# uicc.net
KiCad netlist of a schematic drawn in Altium Designer
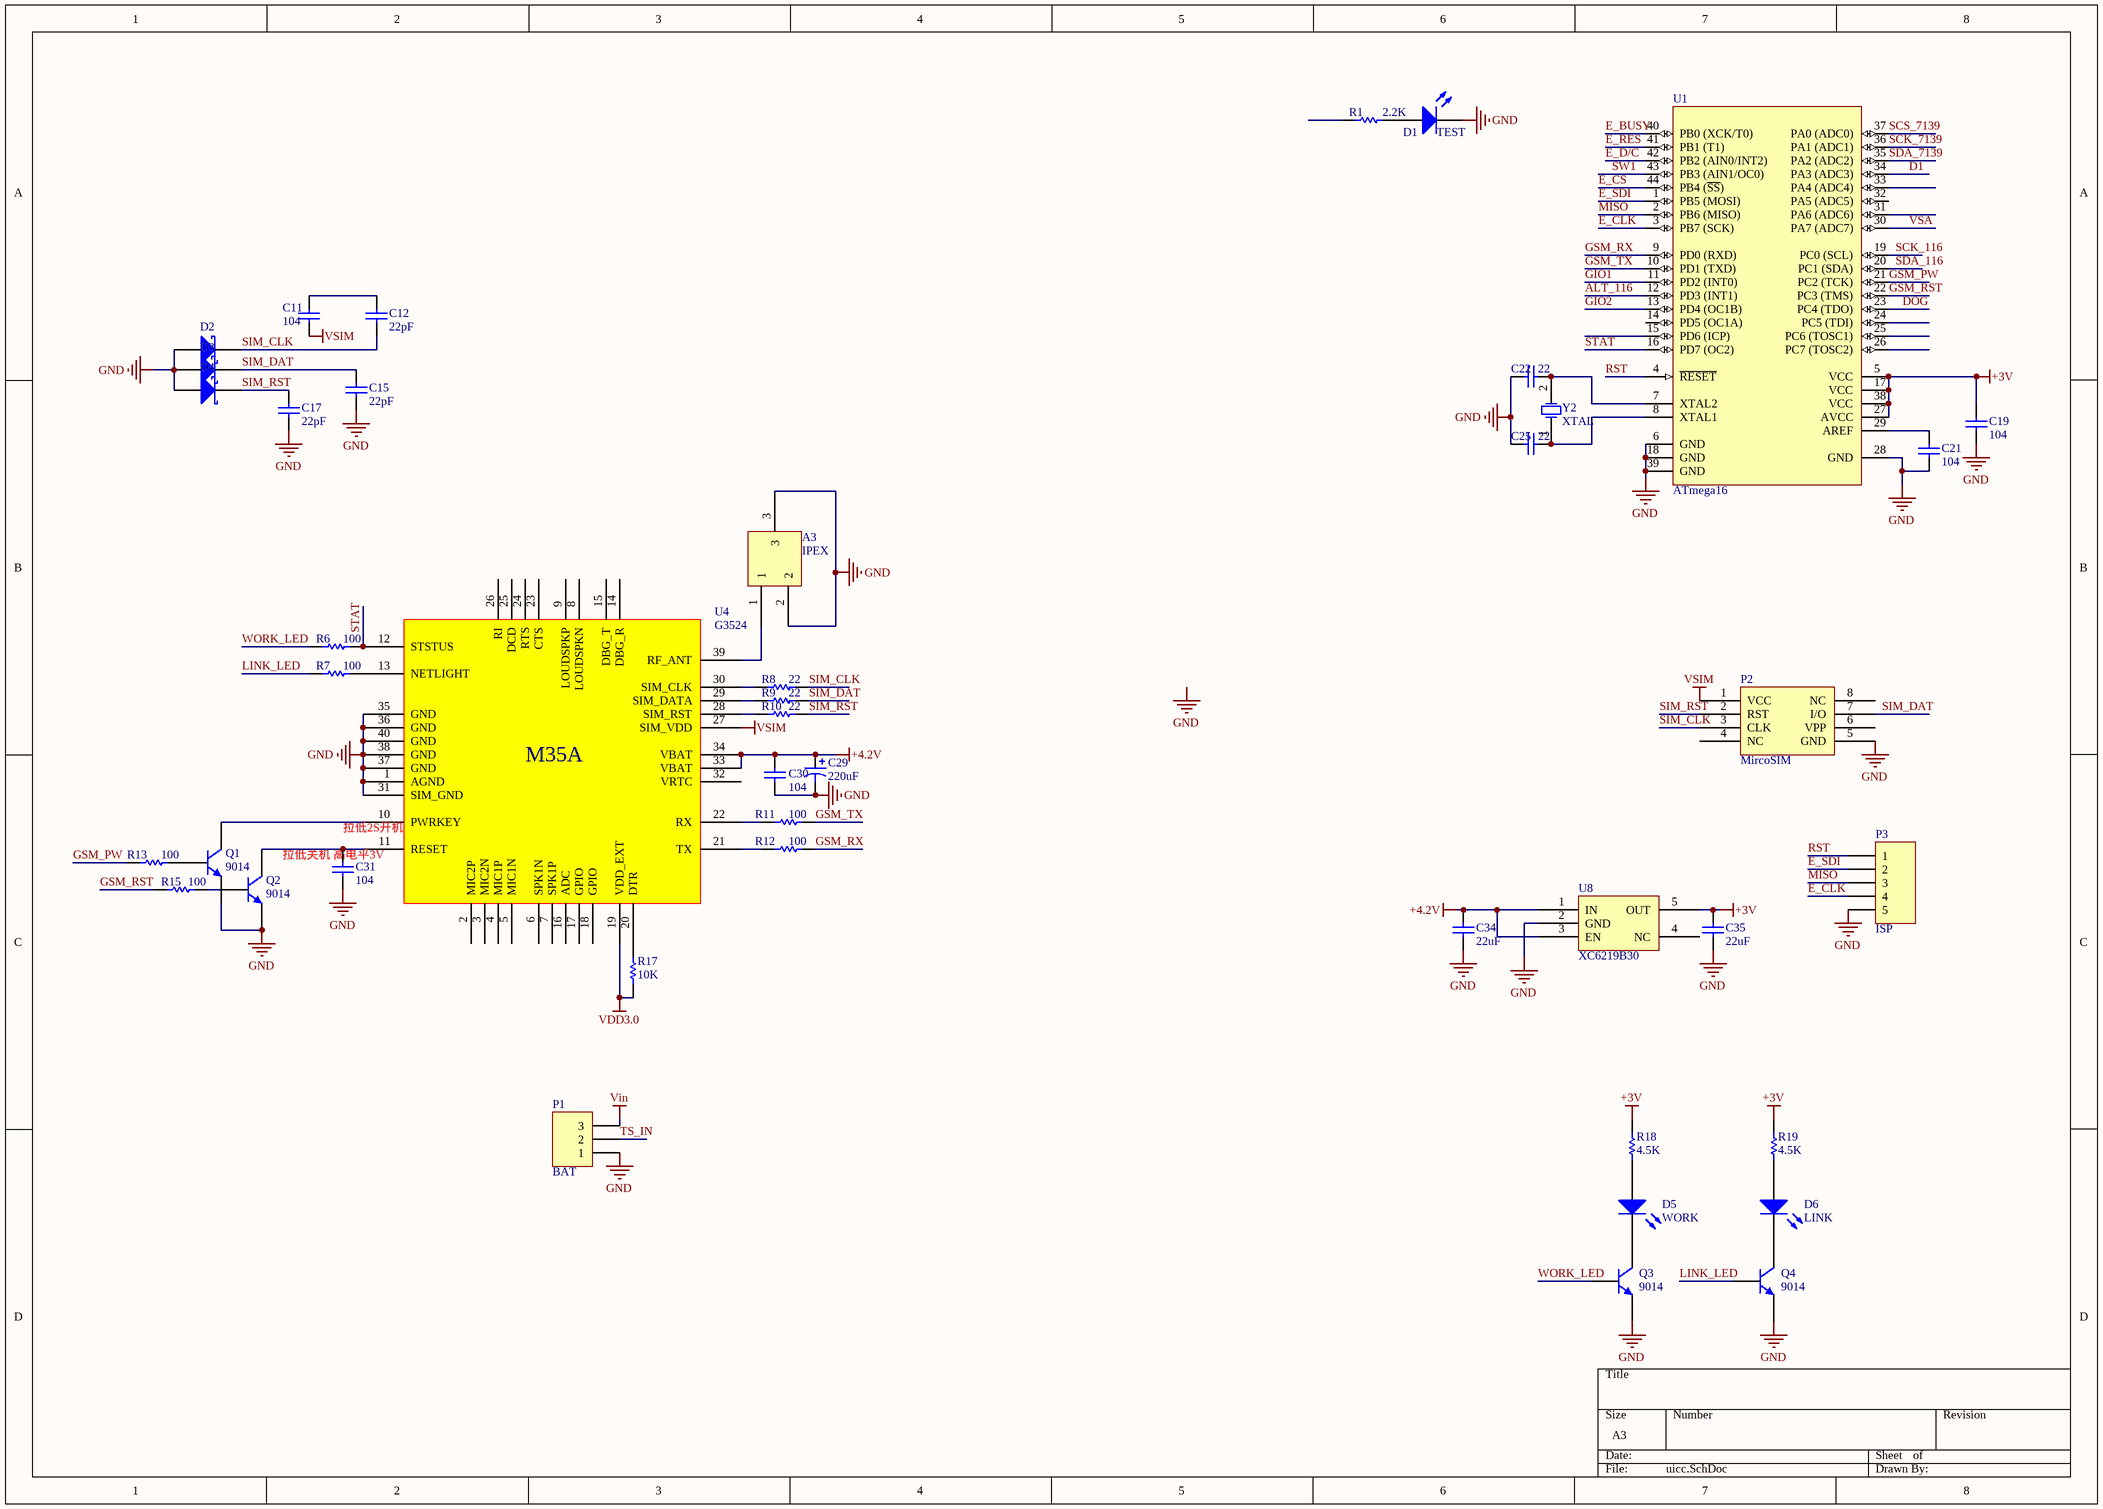
[diagram p0: uicc.SchDoc]

(export (version "E")
  (design (tool "Eeschema 10.0.6"))
  (components
    (comp (ref "A3") (value "IPEX") (footprint "IPEX") (libsource (lib "TANK") (part "IPEX")))
    (comp (ref "C11")
      (value "104")
      (footprint "0603")
      (description "Capacitor")
      (fields (field (name "Comment") "Cap") (field (name "PUBLISHER") "Altium Limited"))
      (libsource (lib "Miscellaneous Devices") (part "Cap"))
    )
    (comp (ref "C12")
      (value "22pF")
      (footprint "0603")
      (description "Capacitor")
      (fields (field (name "Comment") "Cap") (field (name "PUBLISHER") "Altium Limited"))
      (libsource (lib "Miscellaneous Devices") (part "Cap"))
    )
    (comp (ref "C15")
      (value "22pF")
      (footprint "0603")
      (description "Capacitor")
      (fields (field (name "Comment") "Cap") (field (name "PUBLISHER") "Altium Limited"))
      (libsource (lib "Miscellaneous Devices") (part "Cap"))
    )
    (comp (ref "C17")
      (value "22pF")
      (footprint "0603")
      (description "Capacitor")
      (fields (field (name "Comment") "Cap") (field (name "PUBLISHER") "Altium Limited"))
      (libsource (lib "Miscellaneous Devices") (part "Cap"))
    )
    (comp (ref "C19")
      (value "104")
      (footprint "0603")
      (description "Capacitor")
      (fields (field (name "Comment") "Cap") (field (name "PUBLISHER") "Altium Limited"))
      (libsource (lib "Miscellaneous Devices") (part "Cap"))
    )
    (comp (ref "C21")
      (value "104")
      (footprint "0603")
      (description "Capacitor")
      (fields (field (name "Comment") "Cap") (field (name "PUBLISHER") "Altium Limited"))
      (libsource (lib "Miscellaneous Devices") (part "Cap"))
    )
    (comp (ref "C22")
      (value "22")
      (footprint "0603")
      (description "Capacitor")
      (fields (field (name "Comment") "Cap") (field (name "PUBLISHER") "Altium Limited"))
      (libsource (lib "Miscellaneous Devices") (part "Cap"))
    )
    (comp (ref "C25")
      (value "22")
      (footprint "0603")
      (description "Capacitor")
      (fields (field (name "Comment") "Cap") (field (name "PUBLISHER") "Altium Limited"))
      (libsource (lib "Miscellaneous Devices") (part "Cap"))
    )
    (comp (ref "C29")
      (value "220uF")
      (footprint "C7343")
      (description "Polarized Capacitor (Surface Mount)")
      (fields (field (name "Comment") "Cap Pol3") (field (name "PUBLISHER") "Altium Limited"))
      (libsource (lib "Miscellaneous Devices") (part "Cap Pol3"))
    )
    (comp (ref "C30")
      (value "104")
      (footprint "0603")
      (description "Capacitor")
      (fields (field (name "Comment") "Cap") (field (name "PUBLISHER") "Altium Limited"))
      (libsource (lib "Miscellaneous Devices") (part "Cap"))
    )
    (comp (ref "C31")
      (value "104")
      (footprint "0603")
      (description "Capacitor")
      (fields (field (name "Comment") "Cap") (field (name "PUBLISHER") "Altium Limited"))
      (libsource (lib "Miscellaneous Devices") (part "Cap"))
    )
    (comp (ref "C34")
      (value "22uF")
      (footprint "3216[1206]")
      (description "Capacitor")
      (fields (field (name "Comment") "Cap") (field (name "PUBLISHER") "Altium Limited"))
      (libsource (lib "Miscellaneous Devices") (part "Cap"))
    )
    (comp (ref "C35")
      (value "22uF")
      (footprint "3216[1206]")
      (description "Capacitor")
      (fields (field (name "Comment") "Cap") (field (name "PUBLISHER") "Altium Limited"))
      (libsource (lib "Miscellaneous Devices") (part "Cap"))
    )
    (comp (ref "D1")
      (value "TEST")
      (footprint "0603-LED")
      (description "Typical RED, GREEN, YELLOW, AMBER GaAs LED")
      (fields (field (name "PUBLISHER") "Altium Limited"))
      (libsource (lib "Miscellaneous Devices") (part "LED2"))
    )
    (comp (ref "D2")
      (value "RL0603E012M100K")
      (footprint "0603")
      (description "Schottky Rectifier")
      (fields (field (name "PUBLISHER") "Altium Limited"))
      (libsource (lib "Miscellaneous Devices") (part "Diode 18TQ045"))
    )
    (comp (ref "D3")
      (value "RL0603E012M100K")
      (footprint "0603")
      (description "Schottky Rectifier")
      (fields (field (name "PUBLISHER") "Altium Limited"))
      (libsource (lib "Miscellaneous Devices") (part "Diode 18TQ045"))
    )
    (comp (ref "D4")
      (value "RL0603E012M100K")
      (footprint "0603")
      (description "Schottky Rectifier")
      (fields (field (name "PUBLISHER") "Altium Limited"))
      (libsource (lib "Miscellaneous Devices") (part "Diode 18TQ045"))
    )
    (comp (ref "D5")
      (value "WORK")
      (footprint "0603-LED")
      (description "Typical RED, GREEN, YELLOW, AMBER GaAs LED")
      (fields (field (name "PUBLISHER") "Altium Limited"))
      (libsource (lib "Miscellaneous Devices") (part "LED2"))
    )
    (comp (ref "D6")
      (value "LINK")
      (footprint "0603-LED")
      (description "Typical RED, GREEN, YELLOW, AMBER GaAs LED")
      (fields (field (name "PUBLISHER") "Altium Limited"))
      (libsource (lib "Miscellaneous Devices") (part "LED2"))
    )
    (comp (ref "P1")
      (value "BAT")
      (footprint "1.25-3P")
      (description "Header, 3-Pin")
      (fields (field (name "PUBLISHER") "Altium Limited"))
      (libsource (lib "Miscellaneous Connectors") (part "Header 3"))
    )
    (comp (ref "P2") (value "MircoSIM") (footprint "Micro SIM") (libsource (lib "TANK") (part "MircoSIM")))
    (comp (ref "P3")
      (value "ISP")
      (footprint "HDR1X5")
      (description "Header, 5-Pin")
      (fields (field (name "PUBLISHER") "Altium Limited"))
      (libsource (lib "Miscellaneous Connectors") (part "Header 5"))
    )
    (comp (ref "Q1")
      (value "9014")
      (footprint "SOT-23-NPN")
      (description "NPN General Purpose Amplifier")
      (fields (field (name "Comment") "NPN") (field (name "PUBLISHER") "Altium Limited"))
      (libsource (lib "FSC Discrete BJT") (part "2N5551"))
    )
    (comp (ref "Q2")
      (value "9014")
      (footprint "SOT-23-NPN")
      (description "NPN General Purpose Amplifier")
      (fields (field (name "Comment") "NPN") (field (name "PUBLISHER") "Altium Limited"))
      (libsource (lib "FSC Discrete BJT") (part "2N5551"))
    )
    (comp (ref "Q3")
      (value "9014")
      (footprint "SOT-23-NPN")
      (description "NPN General Purpose Amplifier")
      (fields (field (name "Comment") "NPN") (field (name "PUBLISHER") "Altium Limited"))
      (libsource (lib "FSC Discrete BJT") (part "2N5551"))
    )
    (comp (ref "Q4")
      (value "9014")
      (footprint "SOT-23-NPN")
      (description "NPN General Purpose Amplifier")
      (fields (field (name "Comment") "NPN") (field (name "PUBLISHER") "Altium Limited"))
      (libsource (lib "FSC Discrete BJT") (part "2N5551"))
    )
    (comp (ref "R1")
      (value "2.2K")
      (footprint "0603")
      (description "Resistor")
      (fields (field (name "Comment") "Res1") (field (name "PUBLISHER") "Altium Limited"))
      (libsource (lib "Miscellaneous Devices") (part "Res1"))
    )
    (comp (ref "R6")
      (value "100")
      (footprint "0603")
      (description "Resistor")
      (fields (field (name "Comment") "Res1") (field (name "PUBLISHER") "Altium Limited"))
      (libsource (lib "Miscellaneous Devices") (part "Res1"))
    )
    (comp (ref "R7")
      (value "100")
      (footprint "0603")
      (description "Resistor")
      (fields (field (name "Comment") "Res1") (field (name "PUBLISHER") "Altium Limited"))
      (libsource (lib "Miscellaneous Devices") (part "Res1"))
    )
    (comp (ref "R8")
      (value "22")
      (footprint "0603")
      (description "Resistor")
      (fields (field (name "Comment") "Res1") (field (name "PUBLISHER") "Altium Limited"))
      (libsource (lib "Miscellaneous Devices") (part "Res1"))
    )
    (comp (ref "R9")
      (value "22")
      (footprint "0603")
      (description "Resistor")
      (fields (field (name "Comment") "Res1") (field (name "PUBLISHER") "Altium Limited"))
      (libsource (lib "Miscellaneous Devices") (part "Res1"))
    )
    (comp (ref "R10")
      (value "22")
      (footprint "0603")
      (description "Resistor")
      (fields (field (name "Comment") "Res1") (field (name "PUBLISHER") "Altium Limited"))
      (libsource (lib "Miscellaneous Devices") (part "Res1"))
    )
    (comp (ref "R11")
      (value "100")
      (footprint "0603")
      (description "Resistor")
      (fields (field (name "Comment") "Res1") (field (name "PUBLISHER") "Altium Limited"))
      (libsource (lib "Miscellaneous Devices") (part "Res1"))
    )
    (comp (ref "R12")
      (value "100")
      (footprint "0603")
      (description "Resistor")
      (fields (field (name "Comment") "Res1") (field (name "PUBLISHER") "Altium Limited"))
      (libsource (lib "Miscellaneous Devices") (part "Res1"))
    )
    (comp (ref "R13")
      (value "100")
      (footprint "0603")
      (description "Resistor")
      (fields (field (name "Comment") "Res1") (field (name "PUBLISHER") "Altium Limited"))
      (libsource (lib "Miscellaneous Devices") (part "Res1"))
    )
    (comp (ref "R15")
      (value "100")
      (footprint "0603")
      (description "Resistor")
      (fields (field (name "Comment") "Res1") (field (name "PUBLISHER") "Altium Limited"))
      (libsource (lib "Miscellaneous Devices") (part "Res1"))
    )
    (comp (ref "R17")
      (value "10K")
      (footprint "0603")
      (description "Resistor")
      (fields (field (name "Comment") "Res1") (field (name "PUBLISHER") "Altium Limited"))
      (libsource (lib "Miscellaneous Devices") (part "Res1"))
    )
    (comp (ref "R18")
      (value "4.5K")
      (footprint "0603")
      (description "Resistor")
      (fields (field (name "Comment") "Res1") (field (name "PUBLISHER") "Altium Limited"))
      (libsource (lib "Miscellaneous Devices") (part "Res1"))
    )
    (comp (ref "R19")
      (value "4.5K")
      (footprint "0603")
      (description "Resistor")
      (fields (field (name "Comment") "Res1") (field (name "PUBLISHER") "Altium Limited"))
      (libsource (lib "Miscellaneous Devices") (part "Res1"))
    )
    (comp (ref "U1")
      (value "ATmega16")
      (footprint "44A_M")
      (description "8-Bit AVR Microcontroller with 16K Bytes of In-System Programmable Flash Memory")
      (fields (field (name "PUBLISHER") "Altium Limited"))
      (libsource (lib "*") (part "ATmega16-16AI"))
    )
    (comp (ref "U4") (value "G3524") (footprint "G3524") (libsource (lib "TANK") (part "G3524")))
    (comp (ref "U8") (value "XC6219B30") (footprint "SOT23-5N") (libsource (lib "TANK") (part "LP5907")))
    (comp (ref "Y2")
      (value "XTAL")
      (footprint "XT5032")
      (description "Crystal Oscillator")
      (fields (field (name "PUBLISHER") "Altium Limited"))
      (libsource (lib "Miscellaneous Devices") (part "XTAL"))
    )
  )
  (nets
    (net (code "1") (name "+3V") (class "Default")
      (node (ref "C19") (pin "1") (pinfunction "1_1") (pintype "passive"))
      (node (ref "C35") (pin "1") (pinfunction "1_1") (pintype "passive"))
      (node (ref "R18") (pin "1") (pinfunction "1_1") (pintype "passive"))
      (node (ref "R19") (pin "1") (pinfunction "1_1") (pintype "passive"))
      (node (ref "U1") (pin "17") (pinfunction "VCC_17") (pintype "power_in"))
      (node (ref "U1") (pin "27") (pinfunction "AVCC_27") (pintype "power_in"))
      (node (ref "U1") (pin "38") (pinfunction "VCC_38") (pintype "power_in"))
      (node (ref "U1") (pin "5") (pinfunction "VCC_5") (pintype "power_in"))
      (node (ref "U8") (pin "5") (pinfunction "OUT_5") (pintype "passive"))
    )
    (net (code "2") (name "+4.2V") (class "Default")
      (node (ref "C29") (pin "1") (pinfunction "1_1") (pintype "passive"))
      (node (ref "C30") (pin "2") (pinfunction "2_2") (pintype "passive"))
      (node (ref "C34") (pin "1") (pinfunction "1_1") (pintype "passive"))
      (node (ref "U4") (pin "33") (pinfunction "VBAT_33") (pintype "passive"))
      (node (ref "U4") (pin "34") (pinfunction "VBAT_34") (pintype "passive"))
      (node (ref "U8") (pin "1") (pinfunction "IN_1") (pintype "passive"))
      (node (ref "U8") (pin "3") (pinfunction "EN_3") (pintype "passive"))
    )
    (net (code "3") (name "/ALT_116") (class "Default")
      (node (ref "U1") (pin "12") (pinfunction "PD3_(INT1)_12") (pintype "bidirectional"))
    )
    (net (code "4") (name "/D1") (class "Default")
      (node (ref "U1") (pin "34") (pinfunction "PA3_(ADC3)_34") (pintype "bidirectional"))
    )
    (net (code "5") (name "/DOG") (class "Default")
      (node (ref "U1") (pin "23") (pinfunction "PC4_(TDO)_23") (pintype "bidirectional"))
    )
    (net (code "6") (name "/E_BUSY") (class "Default")
      (node (ref "U1") (pin "40") (pinfunction "PB0_(XCK/T0)_40") (pintype "bidirectional"))
    )
    (net (code "7") (name "/E_CLK") (class "Default")
      (node (ref "P3") (pin "4") (pinfunction "4_4") (pintype "passive"))
      (node (ref "U1") (pin "3") (pinfunction "PB7_(SCK)_3") (pintype "bidirectional"))
    )
    (net (code "8") (name "/E_CS") (class "Default")
      (node (ref "U1") (pin "44") (pinfunction "PB4_(~{SS})_44") (pintype "bidirectional"))
    )
    (net (code "9") (name "/E_D{slash}C") (class "Default")
      (node (ref "U1") (pin "42") (pinfunction "PB2_(AIN0/INT2)_42") (pintype "bidirectional"))
    )
    (net (code "10") (name "/E_RES") (class "Default")
      (node (ref "U1") (pin "41") (pinfunction "PB1_(T1)_41") (pintype "bidirectional"))
    )
    (net (code "11") (name "/E_SDI") (class "Default")
      (node (ref "P3") (pin "2") (pinfunction "2_2") (pintype "passive"))
      (node (ref "U1") (pin "1") (pinfunction "PB5_(MOSI)_1") (pintype "bidirectional"))
    )
    (net (code "12") (name "/GIO1") (class "Default")
      (node (ref "U1") (pin "11") (pinfunction "PD2_(INT0)_11") (pintype "bidirectional"))
    )
    (net (code "13") (name "/GIO2") (class "Default")
      (node (ref "U1") (pin "13") (pinfunction "PD4_(OC1B)_13") (pintype "bidirectional"))
    )
    (net (code "14") (name "/GSM_PW") (class "Default")
      (node (ref "R13") (pin "2") (pinfunction "2_2") (pintype "passive"))
      (node (ref "U1") (pin "21") (pinfunction "PC2_(TCK)_21") (pintype "bidirectional"))
    )
    (net (code "15") (name "/GSM_RST") (class "Default")
      (node (ref "R15") (pin "2") (pinfunction "2_2") (pintype "passive"))
      (node (ref "U1") (pin "22") (pinfunction "PC3_(TMS)_22") (pintype "bidirectional"))
    )
    (net (code "16") (name "/GSM_RX") (class "Default")
      (node (ref "R12") (pin "2") (pinfunction "2_2") (pintype "passive"))
      (node (ref "U1") (pin "9") (pinfunction "PD0_(RXD)_9") (pintype "bidirectional"))
    )
    (net (code "17") (name "/GSM_TX") (class "Default")
      (node (ref "R11") (pin "2") (pinfunction "2_2") (pintype "passive"))
      (node (ref "U1") (pin "10") (pinfunction "PD1_(TXD)_10") (pintype "bidirectional"))
    )
    (net (code "18") (name "/LINK_LED") (class "Default")
      (node (ref "Q4") (pin "2") (pinfunction "B_2") (pintype "passive"))
      (node (ref "R7") (pin "2") (pinfunction "2_2") (pintype "passive"))
    )
    (net (code "19") (name "/MISO") (class "Default")
      (node (ref "P3") (pin "3") (pinfunction "3_3") (pintype "passive"))
      (node (ref "U1") (pin "2") (pinfunction "PB6_(MISO)_2") (pintype "bidirectional"))
    )
    (net (code "20") (name "/RST") (class "Default")
      (node (ref "P3") (pin "1") (pinfunction "1_1") (pintype "passive"))
      (node (ref "U1") (pin "4") (pinfunction "~{RESET}_4") (pintype "input"))
    )
    (net (code "21") (name "/SCK_116") (class "Default")
      (node (ref "U1") (pin "19") (pinfunction "PC0_(SCL)_19") (pintype "bidirectional"))
    )
    (net (code "22") (name "/SCK_7139") (class "Default")
      (node (ref "U1") (pin "36") (pinfunction "PA1_(ADC1)_36") (pintype "bidirectional"))
    )
    (net (code "23") (name "/SCS_7139") (class "Default")
      (node (ref "U1") (pin "37") (pinfunction "PA0_(ADC0)_37") (pintype "bidirectional"))
    )
    (net (code "24") (name "/SDA_116") (class "Default")
      (node (ref "U1") (pin "20") (pinfunction "PC1_(SDA)_20") (pintype "bidirectional"))
    )
    (net (code "25") (name "/SDA_7139") (class "Default")
      (node (ref "U1") (pin "35") (pinfunction "PA2_(ADC2)_35") (pintype "bidirectional"))
    )
    (net (code "26") (name "/SIM_CLK") (class "Default")
      (node (ref "C12") (pin "2") (pinfunction "2_2") (pintype "passive"))
      (node (ref "D2") (pin "1") (pinfunction "K_1") (pintype "passive"))
      (node (ref "P2") (pin "3") (pinfunction "CLK_3") (pintype "passive"))
      (node (ref "R8") (pin "1") (pinfunction "1_1") (pintype "passive"))
    )
    (net (code "27") (name "/SIM_DAT") (class "Default")
      (node (ref "C15") (pin "1") (pinfunction "1_1") (pintype "passive"))
      (node (ref "D3") (pin "1") (pinfunction "K_1") (pintype "passive"))
      (node (ref "P2") (pin "7") (pinfunction "I/O_7") (pintype "passive"))
      (node (ref "R9") (pin "1") (pinfunction "1_1") (pintype "passive"))
    )
    (net (code "28") (name "/SIM_RST") (class "Default")
      (node (ref "C17") (pin "1") (pinfunction "1_1") (pintype "passive"))
      (node (ref "D4") (pin "1") (pinfunction "K_1") (pintype "passive"))
      (node (ref "P2") (pin "2") (pinfunction "RST_2") (pintype "passive"))
      (node (ref "R10") (pin "1") (pinfunction "1_1") (pintype "passive"))
    )
    (net (code "29") (name "/STAT") (class "Default")
      (node (ref "R6") (pin "1") (pinfunction "1_1") (pintype "passive"))
      (node (ref "U1") (pin "16") (pinfunction "PD7_(OC2)_16") (pintype "bidirectional"))
      (node (ref "U4") (pin "12") (pinfunction "STSTUS_12") (pintype "passive"))
    )
    (net (code "30") (name "/SW1") (class "Default")
      (node (ref "U1") (pin "43") (pinfunction "PB3_(AIN1/OC0)_43") (pintype "bidirectional"))
    )
    (net (code "31") (name "/TS_IN") (class "Default")
      (node (ref "P1") (pin "2") (pinfunction "2_2") (pintype "passive"))
    )
    (net (code "32") (name "/VSA") (class "Default")
      (node (ref "U1") (pin "30") (pinfunction "PA7_(ADC7)_30") (pintype "bidirectional"))
    )
    (net (code "33") (name "/WORK_LED") (class "Default")
      (node (ref "Q3") (pin "2") (pinfunction "B_2") (pintype "passive"))
      (node (ref "R6") (pin "2") (pinfunction "2_2") (pintype "passive"))
    )
    (net (code "34") (name "GND") (class "Default")
      (node (ref "A3") (pin "2") (pinfunction "2_2") (pintype "passive"))
      (node (ref "A3") (pin "3") (pinfunction "3_3") (pintype "passive"))
      (node (ref "C15") (pin "2") (pinfunction "2_2") (pintype "passive"))
      (node (ref "C17") (pin "2") (pinfunction "2_2") (pintype "passive"))
      (node (ref "C19") (pin "2") (pinfunction "2_2") (pintype "passive"))
      (node (ref "C21") (pin "2") (pinfunction "2_2") (pintype "passive"))
      (node (ref "C22") (pin "2") (pinfunction "2_2") (pintype "passive"))
      (node (ref "C25") (pin "2") (pinfunction "2_2") (pintype "passive"))
      (node (ref "C29") (pin "2") (pinfunction "2_2") (pintype "passive"))
      (node (ref "C30") (pin "1") (pinfunction "1_1") (pintype "passive"))
      (node (ref "C31") (pin "2") (pinfunction "2_2") (pintype "passive"))
      (node (ref "C34") (pin "2") (pinfunction "2_2") (pintype "passive"))
      (node (ref "C35") (pin "2") (pinfunction "2_2") (pintype "passive"))
      (node (ref "D1") (pin "2") (pinfunction "K_2") (pintype "passive"))
      (node (ref "D2") (pin "2") (pinfunction "A_2") (pintype "passive"))
      (node (ref "D3") (pin "2") (pinfunction "A_2") (pintype "passive"))
      (node (ref "D4") (pin "2") (pinfunction "A_2") (pintype "passive"))
      (node (ref "P1") (pin "1") (pinfunction "1_1") (pintype "passive"))
      (node (ref "P2") (pin "5") (pinfunction "GND_5") (pintype "passive"))
      (node (ref "P3") (pin "5") (pinfunction "5_5") (pintype "passive"))
      (node (ref "Q1") (pin "1") (pinfunction "E_1") (pintype "passive"))
      (node (ref "Q2") (pin "1") (pinfunction "E_1") (pintype "passive"))
      (node (ref "Q3") (pin "1") (pinfunction "E_1") (pintype "passive"))
      (node (ref "Q4") (pin "1") (pinfunction "E_1") (pintype "passive"))
      (node (ref "U1") (pin "18") (pinfunction "GND_18") (pintype "power_in"))
      (node (ref "U1") (pin "28") (pinfunction "GND_28") (pintype "power_in"))
      (node (ref "U1") (pin "39") (pinfunction "GND_39") (pintype "power_in"))
      (node (ref "U1") (pin "6") (pinfunction "GND_6") (pintype "power_in"))
      (node (ref "U4") (pin "1") (pinfunction "AGND_1") (pintype "passive"))
      (node (ref "U4") (pin "31") (pinfunction "SIM_GND_31") (pintype "passive"))
      (node (ref "U4") (pin "35") (pinfunction "GND_35") (pintype "passive"))
      (node (ref "U4") (pin "36") (pinfunction "GND_36") (pintype "passive"))
      (node (ref "U4") (pin "37") (pinfunction "GND_37") (pintype "passive"))
      (node (ref "U4") (pin "38") (pinfunction "GND_38") (pintype "passive"))
      (node (ref "U4") (pin "40") (pinfunction "GND_40") (pintype "passive"))
      (node (ref "U8") (pin "2") (pinfunction "GND_2") (pintype "passive"))
    )
    (net (code "35") (name "Net-(C11-Pad1)") (class "Default")
      (node (ref "C11") (pin "1") (pinfunction "1_1") (pintype "passive"))
      (node (ref "C12") (pin "1") (pinfunction "1_1") (pintype "passive"))
    )
    (net (code "36") (name "Net-(D1-A)") (class "Default")
      (node (ref "D1") (pin "1") (pinfunction "A_1") (pintype "passive"))
      (node (ref "R1") (pin "2") (pinfunction "2_2") (pintype "passive"))
    )
    (net (code "37") (name "Net-(D5-A)") (class "Default")
      (node (ref "D5") (pin "1") (pinfunction "A_1") (pintype "passive"))
      (node (ref "R18") (pin "2") (pinfunction "2_2") (pintype "passive"))
    )
    (net (code "38") (name "Net-(D5-K)") (class "Default")
      (node (ref "D5") (pin "2") (pinfunction "K_2") (pintype "passive"))
      (node (ref "Q3") (pin "3") (pinfunction "C_3") (pintype "passive"))
    )
    (net (code "39") (name "Net-(D6-A)") (class "Default")
      (node (ref "D6") (pin "1") (pinfunction "A_1") (pintype "passive"))
      (node (ref "R19") (pin "2") (pinfunction "2_2") (pintype "passive"))
    )
    (net (code "40") (name "Net-(D6-K)") (class "Default")
      (node (ref "D6") (pin "2") (pinfunction "K_2") (pintype "passive"))
      (node (ref "Q4") (pin "3") (pinfunction "C_3") (pintype "passive"))
    )
    (net (code "41") (name "Net-(Q1-B)") (class "Default")
      (node (ref "Q1") (pin "2") (pinfunction "B_2") (pintype "passive"))
      (node (ref "R13") (pin "1") (pinfunction "1_1") (pintype "passive"))
    )
    (net (code "42") (name "Net-(Q1-C)") (class "Default")
      (node (ref "Q1") (pin "3") (pinfunction "C_3") (pintype "passive"))
      (node (ref "U4") (pin "10") (pinfunction "PWRKEY_10") (pintype "passive"))
    )
    (net (code "43") (name "Net-(Q2-B)") (class "Default")
      (node (ref "Q2") (pin "2") (pinfunction "B_2") (pintype "passive"))
      (node (ref "R15") (pin "1") (pinfunction "1_1") (pintype "passive"))
    )
    (net (code "44") (name "Net-(Q2-C)") (class "Default")
      (node (ref "C31") (pin "1") (pinfunction "1_1") (pintype "passive"))
      (node (ref "Q2") (pin "3") (pinfunction "C_3") (pintype "passive"))
      (node (ref "U4") (pin "11") (pinfunction "RESET_11") (pintype "passive"))
    )
    (net (code "45") (name "Net-(U1-AREF)") (class "Default")
      (node (ref "C21") (pin "1") (pinfunction "1_1") (pintype "passive"))
      (node (ref "U1") (pin "29") (pinfunction "AREF_29") (pintype "passive"))
    )
    (net (code "46") (name "Net-(U1-XTAL1)") (class "Default")
      (node (ref "C25") (pin "1") (pinfunction "1_1") (pintype "passive"))
      (node (ref "U1") (pin "8") (pinfunction "XTAL1_8") (pintype "passive"))
      (node (ref "Y2") (pin "1") (pinfunction "OSC1_1") (pintype "passive"))
    )
    (net (code "47") (name "Net-(U1-XTAL2)") (class "Default")
      (node (ref "C22") (pin "1") (pinfunction "1_1") (pintype "passive"))
      (node (ref "U1") (pin "7") (pinfunction "XTAL2_7") (pintype "passive"))
      (node (ref "Y2") (pin "2") (pinfunction "OSC2_2") (pintype "passive"))
    )
    (net (code "48") (name "Net-(U4-DTR)") (class "Default")
      (node (ref "R17") (pin "1") (pinfunction "1_1") (pintype "passive"))
      (node (ref "U4") (pin "20") (pinfunction "DTR_20") (pintype "passive"))
    )
    (net (code "49") (name "Net-(U4-NETLIGHT)") (class "Default")
      (node (ref "R7") (pin "1") (pinfunction "1_1") (pintype "passive"))
      (node (ref "U4") (pin "13") (pinfunction "NETLIGHT_13") (pintype "passive"))
    )
    (net (code "50") (name "Net-(U4-RF_ANT)") (class "Default")
      (node (ref "A3") (pin "1") (pinfunction "1_1") (pintype "passive"))
      (node (ref "U4") (pin "39") (pinfunction "RF_ANT_39") (pintype "passive"))
    )
    (net (code "51") (name "Net-(U4-RX)") (class "Default")
      (node (ref "R11") (pin "1") (pinfunction "1_1") (pintype "passive"))
      (node (ref "U4") (pin "22") (pinfunction "RX_22") (pintype "passive"))
    )
    (net (code "52") (name "Net-(U4-SIM_CLK)") (class "Default")
      (node (ref "R8") (pin "2") (pinfunction "2_2") (pintype "passive"))
      (node (ref "U4") (pin "30") (pinfunction "SIM_CLK_30") (pintype "passive"))
    )
    (net (code "53") (name "Net-(U4-SIM_DATA)") (class "Default")
      (node (ref "R9") (pin "2") (pinfunction "2_2") (pintype "passive"))
      (node (ref "U4") (pin "29") (pinfunction "SIM_DATA_29") (pintype "passive"))
    )
    (net (code "54") (name "Net-(U4-SIM_RST)") (class "Default")
      (node (ref "R10") (pin "2") (pinfunction "2_2") (pintype "passive"))
      (node (ref "U4") (pin "28") (pinfunction "SIM_RST_28") (pintype "passive"))
    )
    (net (code "55") (name "Net-(U4-TX)") (class "Default")
      (node (ref "R12") (pin "1") (pinfunction "1_1") (pintype "passive"))
      (node (ref "U4") (pin "21") (pinfunction "TX_21") (pintype "passive"))
    )
    (net (code "56") (name "VDD3.0") (class "Default")
      (node (ref "R17") (pin "2") (pinfunction "2_2") (pintype "passive"))
      (node (ref "U4") (pin "19") (pinfunction "VDD_EXT_19") (pintype "passive"))
    )
    (net (code "57") (name "VSIM") (class "Default")
      (node (ref "C11") (pin "2") (pinfunction "2_2") (pintype "passive"))
      (node (ref "P2") (pin "1") (pinfunction "VCC_1") (pintype "passive"))
      (node (ref "U4") (pin "27") (pinfunction "SIM_VDD_27") (pintype "passive"))
    )
    (net (code "58") (name "Vin") (class "Default")
      (node (ref "P1") (pin "3") (pinfunction "3_3") (pintype "passive"))
    )
    (net (code "59") (name "unconnected-(P2-NC-Pad4)") (class "Default")
      (node (ref "P2") (pin "4") (pinfunction "NC_4") (pintype "passive"))
    )
    (net (code "60") (name "unconnected-(P2-NC-Pad8)") (class "Default")
      (node (ref "P2") (pin "8") (pinfunction "NC_8") (pintype "passive"))
    )
    (net (code "61") (name "unconnected-(P2-VPP-Pad6)") (class "Default")
      (node (ref "P2") (pin "6") (pinfunction "VPP_6") (pintype "passive"))
    )
    (net (code "62") (name "unconnected-(R1-Pad1)") (class "Default")
      (node (ref "R1") (pin "1") (pinfunction "1_1") (pintype "passive"))
    )
    (net (code "63") (name "unconnected-(U1-PA4_(ADC4)-Pad33)") (class "Default")
      (node (ref "U1") (pin "33") (pinfunction "PA4_(ADC4)_33") (pintype "bidirectional"))
    )
    (net (code "64") (name "unconnected-(U1-PA5_(ADC5)-Pad32)") (class "Default")
      (node (ref "U1") (pin "32") (pinfunction "PA5_(ADC5)_32") (pintype "bidirectional"))
    )
    (net (code "65") (name "unconnected-(U1-PA6_(ADC6)-Pad31)") (class "Default")
      (node (ref "U1") (pin "31") (pinfunction "PA6_(ADC6)_31") (pintype "bidirectional"))
    )
    (net (code "66") (name "unconnected-(U1-PC5_(TDI)-Pad24)") (class "Default")
      (node (ref "U1") (pin "24") (pinfunction "PC5_(TDI)_24") (pintype "bidirectional"))
    )
    (net (code "67") (name "unconnected-(U1-PC6_(TOSC1)-Pad25)") (class "Default")
      (node (ref "U1") (pin "25") (pinfunction "PC6_(TOSC1)_25") (pintype "bidirectional"))
    )
    (net (code "68") (name "unconnected-(U1-PC7_(TOSC2)-Pad26)") (class "Default")
      (node (ref "U1") (pin "26") (pinfunction "PC7_(TOSC2)_26") (pintype "bidirectional"))
    )
    (net (code "69") (name "unconnected-(U1-PD5_(OC1A)-Pad14)") (class "Default")
      (node (ref "U1") (pin "14") (pinfunction "PD5_(OC1A)_14") (pintype "bidirectional"))
    )
    (net (code "70") (name "unconnected-(U1-PD6_(ICP)-Pad15)") (class "Default")
      (node (ref "U1") (pin "15") (pinfunction "PD6_(ICP)_15") (pintype "bidirectional"))
    )
    (net (code "71") (name "unconnected-(U4-ADC-Pad16)") (class "Default")
      (node (ref "U4") (pin "16") (pinfunction "ADC_16") (pintype "passive"))
    )
    (net (code "72") (name "unconnected-(U4-CTS-Pad23)") (class "Default")
      (node (ref "U4") (pin "23") (pinfunction "CTS_23") (pintype "passive"))
    )
    (net (code "73") (name "unconnected-(U4-DBG_R-Pad14)") (class "Default")
      (node (ref "U4") (pin "14") (pinfunction "DBG_R_14") (pintype "passive"))
    )
    (net (code "74") (name "unconnected-(U4-DBG_T-Pad15)") (class "Default")
      (node (ref "U4") (pin "15") (pinfunction "DBG_T_15") (pintype "passive"))
    )
    (net (code "75") (name "unconnected-(U4-DCD-Pad25)") (class "Default")
      (node (ref "U4") (pin "25") (pinfunction "DCD_25") (pintype "passive"))
    )
    (net (code "76") (name "unconnected-(U4-GPIO-Pad17)") (class "Default")
      (node (ref "U4") (pin "17") (pinfunction "GPIO_17") (pintype "passive"))
    )
    (net (code "77") (name "unconnected-(U4-GPIO-Pad18)") (class "Default")
      (node (ref "U4") (pin "18") (pinfunction "GPIO_18") (pintype "passive"))
    )
    (net (code "78") (name "unconnected-(U4-LOUDSPKN-Pad8)") (class "Default")
      (node (ref "U4") (pin "8") (pinfunction "LOUDSPKN_8") (pintype "passive"))
    )
    (net (code "79") (name "unconnected-(U4-LOUDSPKP-Pad9)") (class "Default")
      (node (ref "U4") (pin "9") (pinfunction "LOUDSPKP_9") (pintype "passive"))
    )
    (net (code "80") (name "unconnected-(U4-MIC1N-Pad5)") (class "Default")
      (node (ref "U4") (pin "5") (pinfunction "MIC1N_5") (pintype "passive"))
    )
    (net (code "81") (name "unconnected-(U4-MIC1P-Pad4)") (class "Default")
      (node (ref "U4") (pin "4") (pinfunction "MIC1P_4") (pintype "passive"))
    )
    (net (code "82") (name "unconnected-(U4-MIC2N-Pad3)") (class "Default")
      (node (ref "U4") (pin "3") (pinfunction "MIC2N_3") (pintype "passive"))
    )
    (net (code "83") (name "unconnected-(U4-MIC2P-Pad2)") (class "Default")
      (node (ref "U4") (pin "2") (pinfunction "MIC2P_2") (pintype "passive"))
    )
    (net (code "84") (name "unconnected-(U4-RI-Pad26)") (class "Default")
      (node (ref "U4") (pin "26") (pinfunction "RI_26") (pintype "passive"))
    )
    (net (code "85") (name "unconnected-(U4-RTS-Pad24)") (class "Default")
      (node (ref "U4") (pin "24") (pinfunction "RTS_24") (pintype "passive"))
    )
    (net (code "86") (name "unconnected-(U4-SPK1N-Pad6)") (class "Default")
      (node (ref "U4") (pin "6") (pinfunction "SPK1N_6") (pintype "passive"))
    )
    (net (code "87") (name "unconnected-(U4-SPK1P-Pad7)") (class "Default")
      (node (ref "U4") (pin "7") (pinfunction "SPK1P_7") (pintype "passive"))
    )
    (net (code "88") (name "unconnected-(U4-VRTC-Pad32)") (class "Default")
      (node (ref "U4") (pin "32") (pinfunction "VRTC_32") (pintype "passive"))
    )
    (net (code "89") (name "unconnected-(U8-NC-Pad4)") (class "Default")
      (node (ref "U8") (pin "4") (pinfunction "NC_4") (pintype "passive"))
    )
  )
)
